# LED_volume_bar.net
KiCad netlist of a schematic drawn in EAGLE
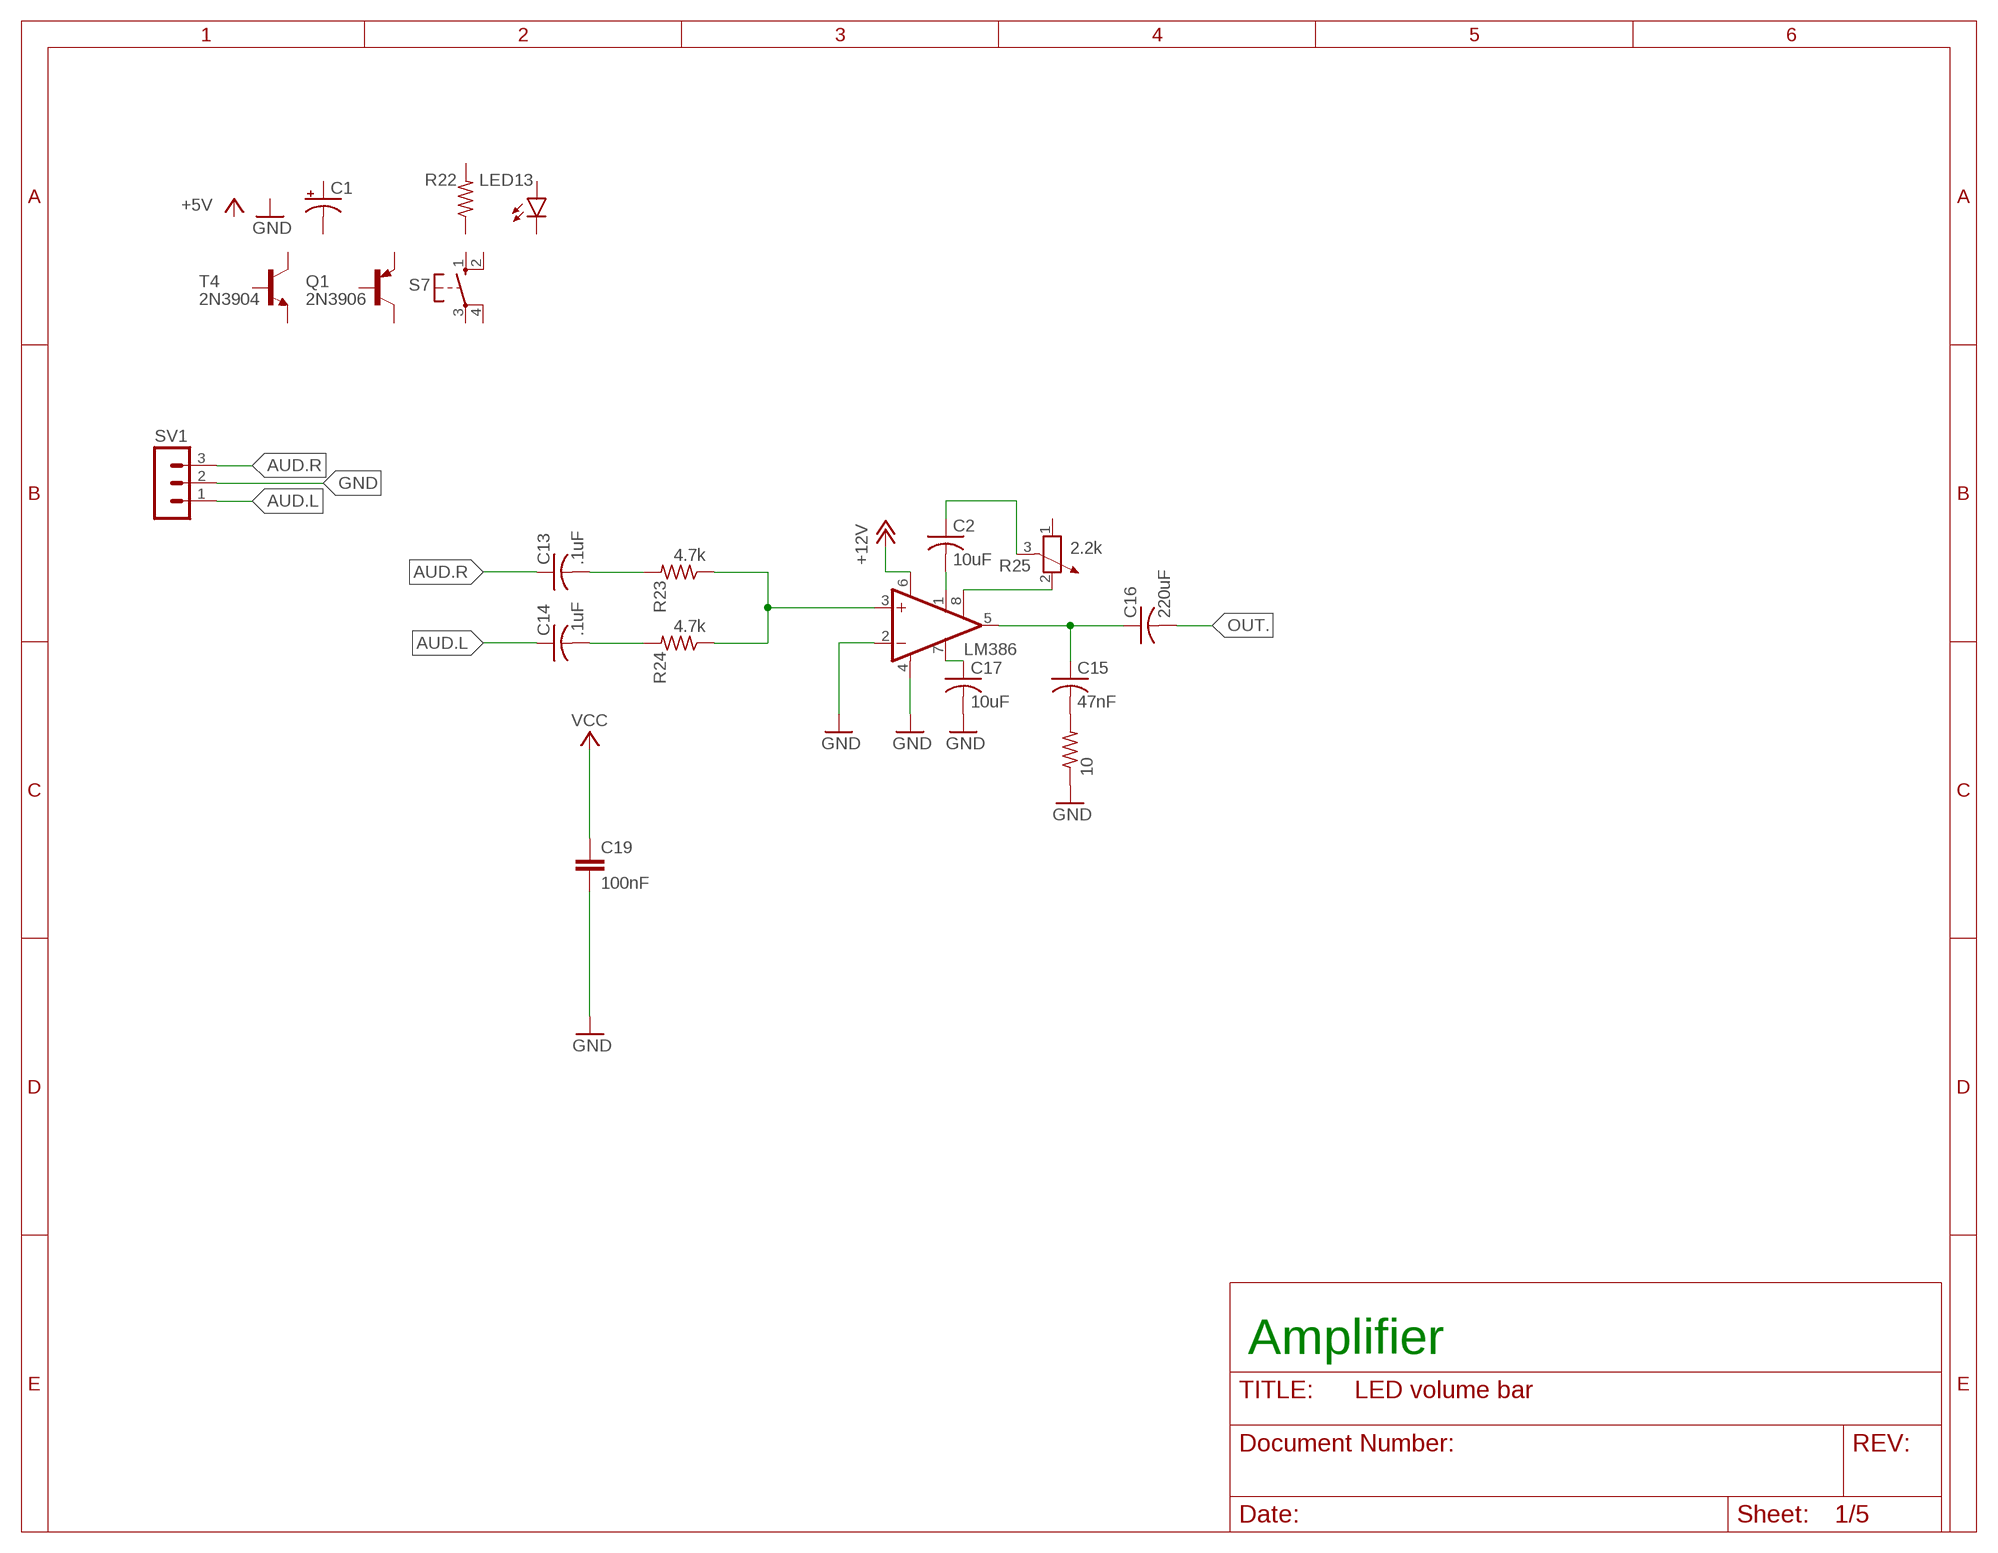
[diagram p0: schematic, sheet 1]
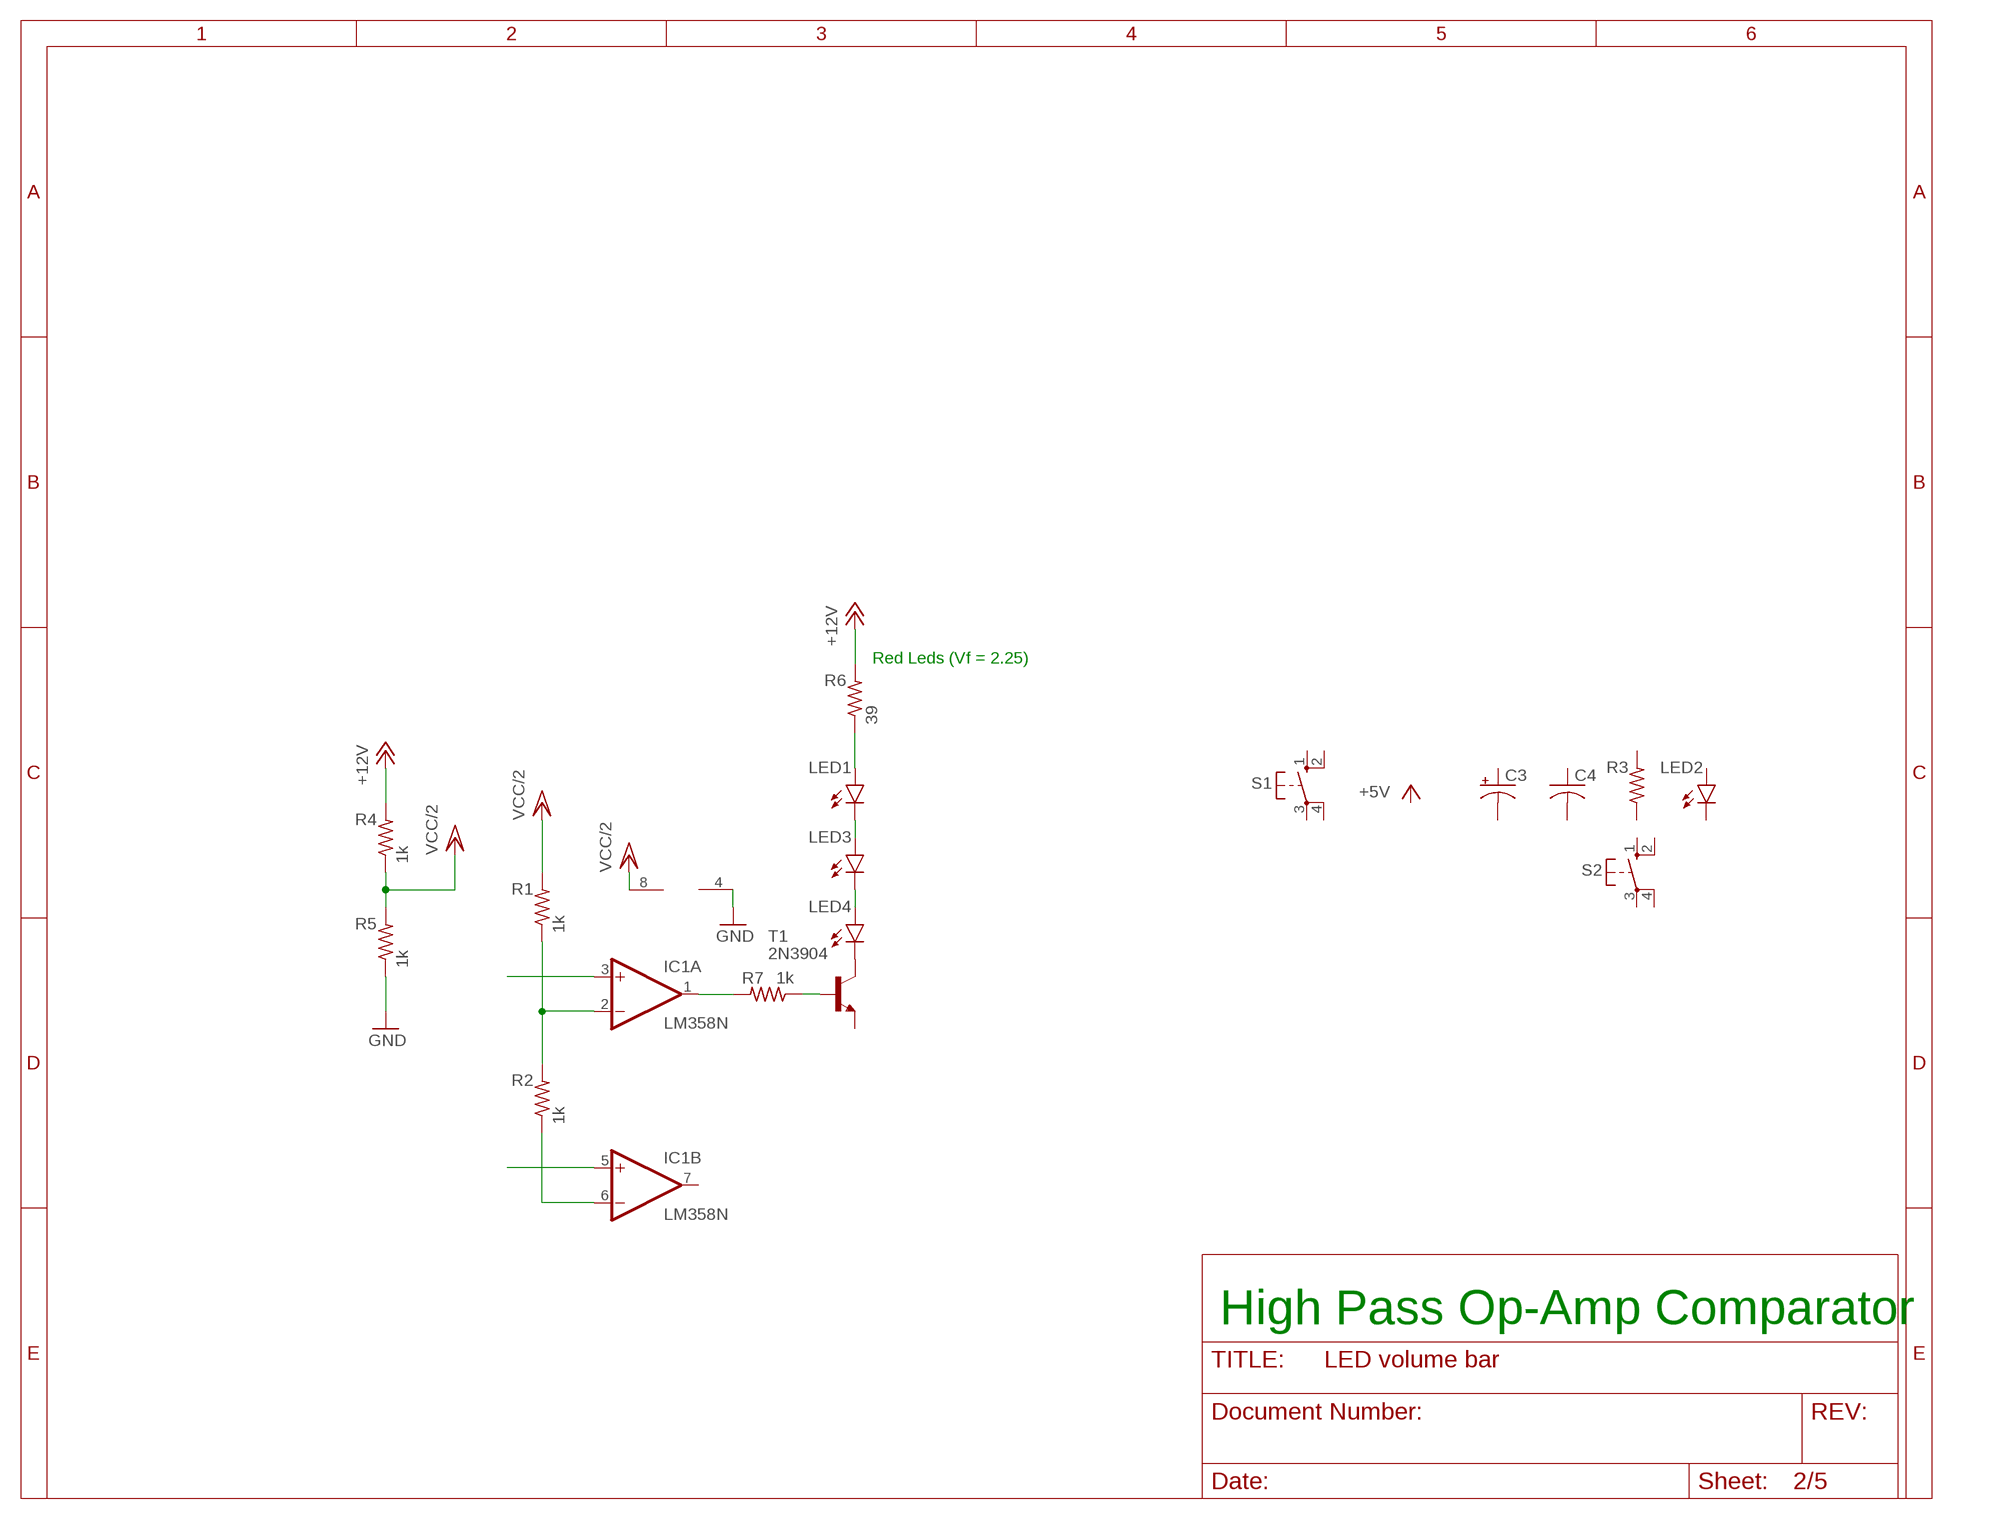
[diagram p1: schematic, sheet 2]
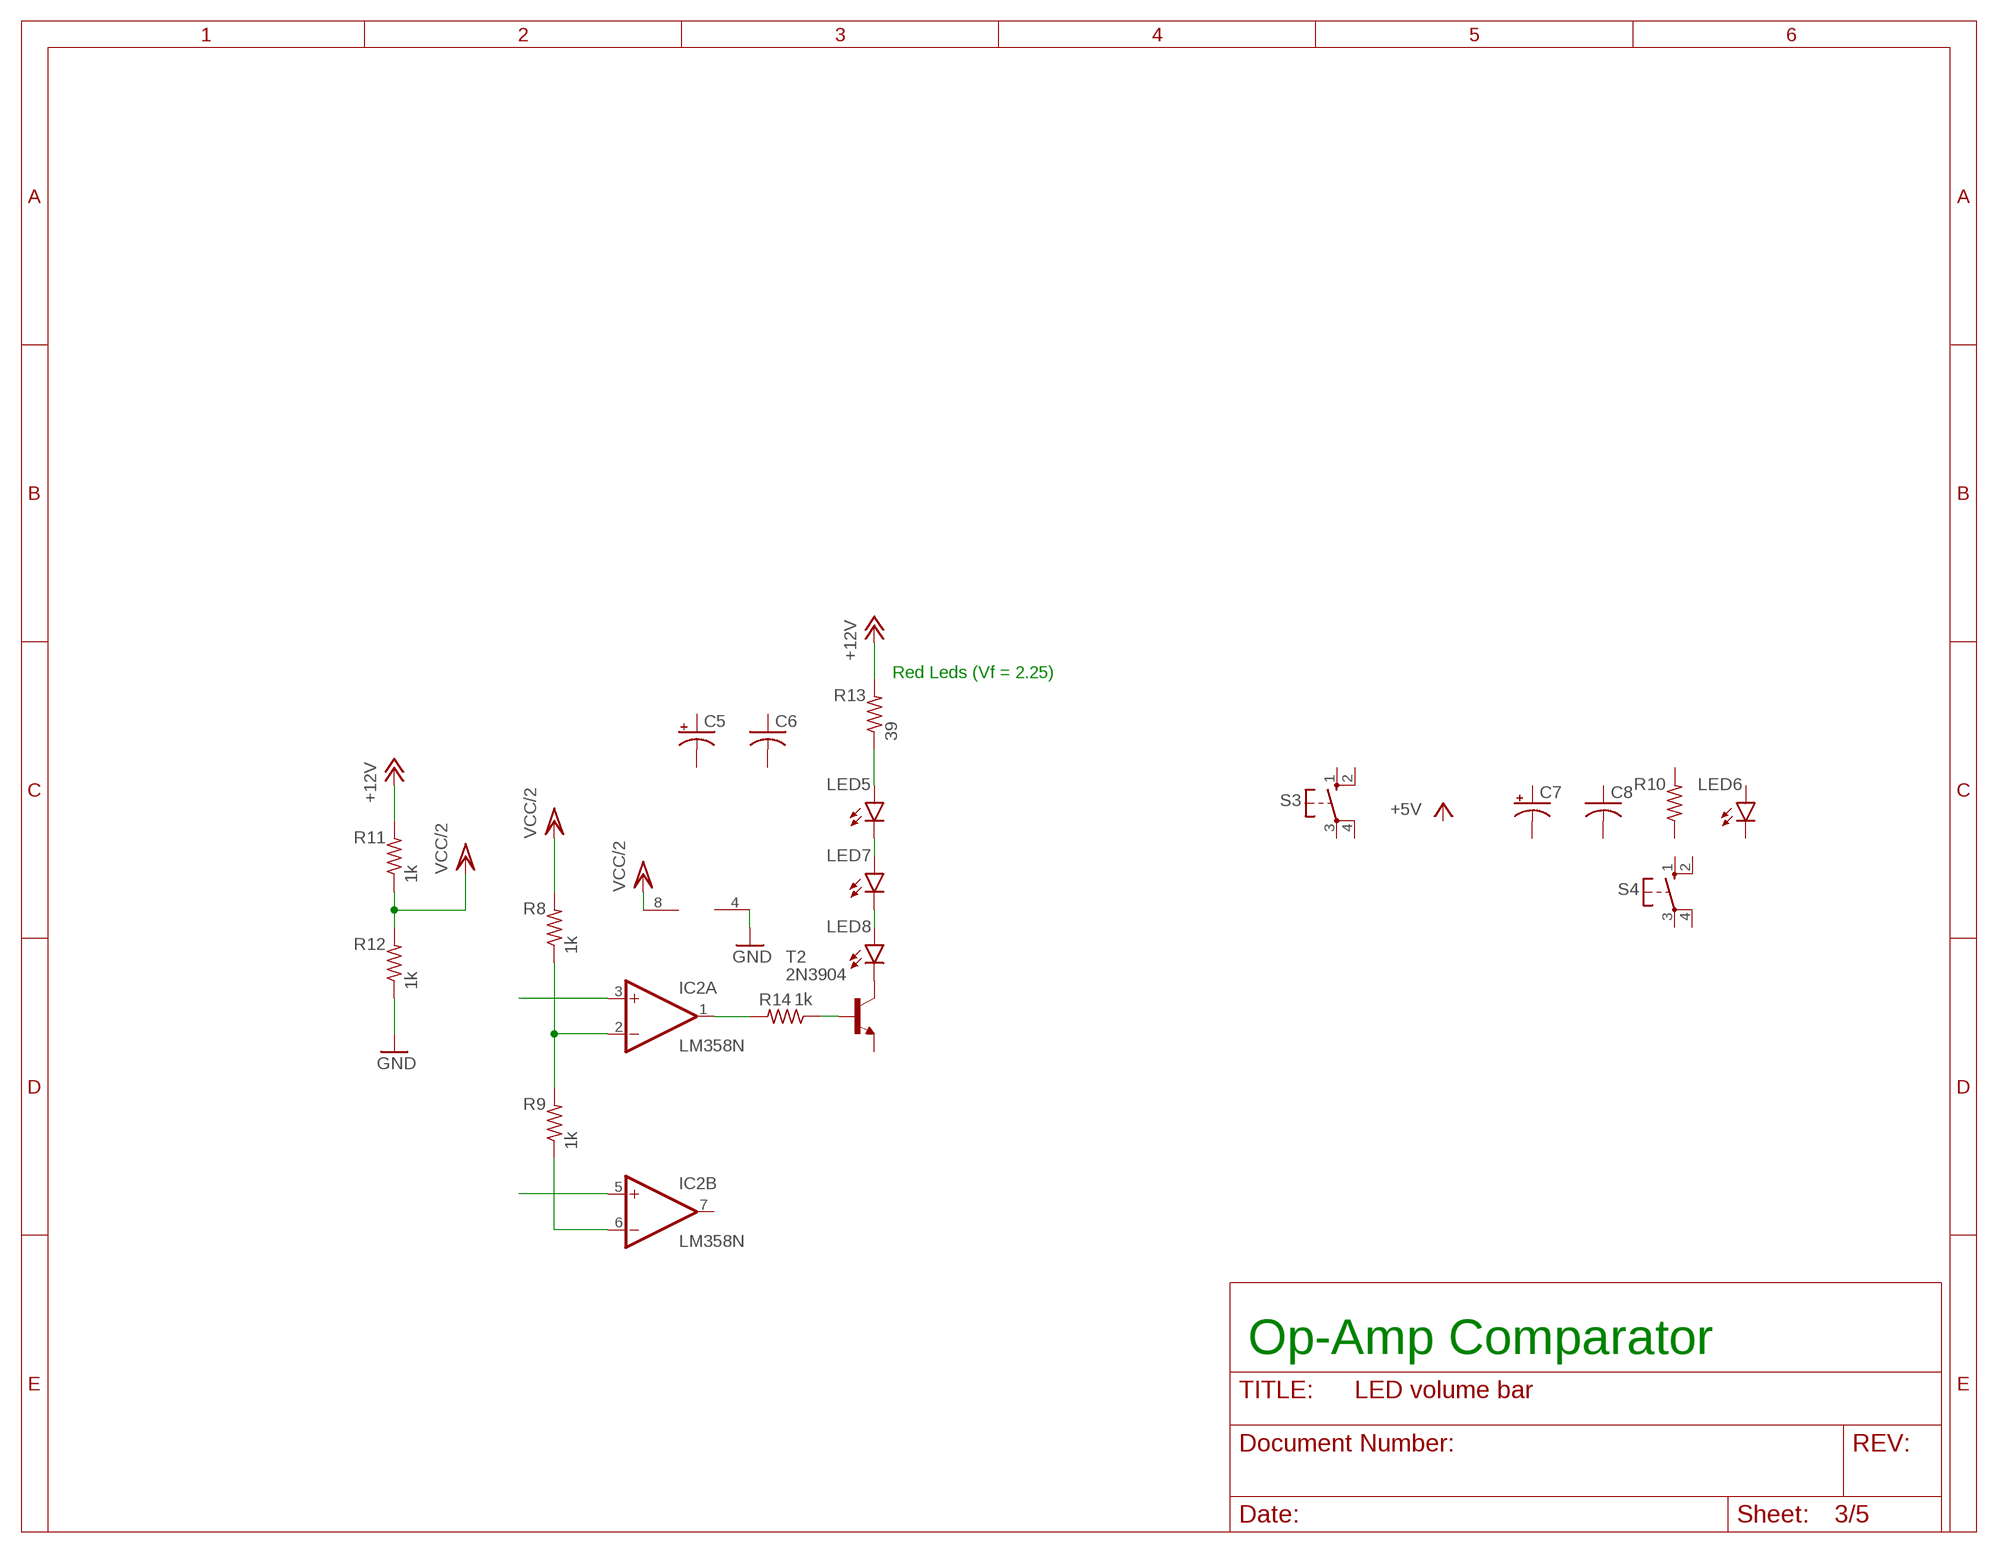
[diagram p2: schematic, sheet 3]
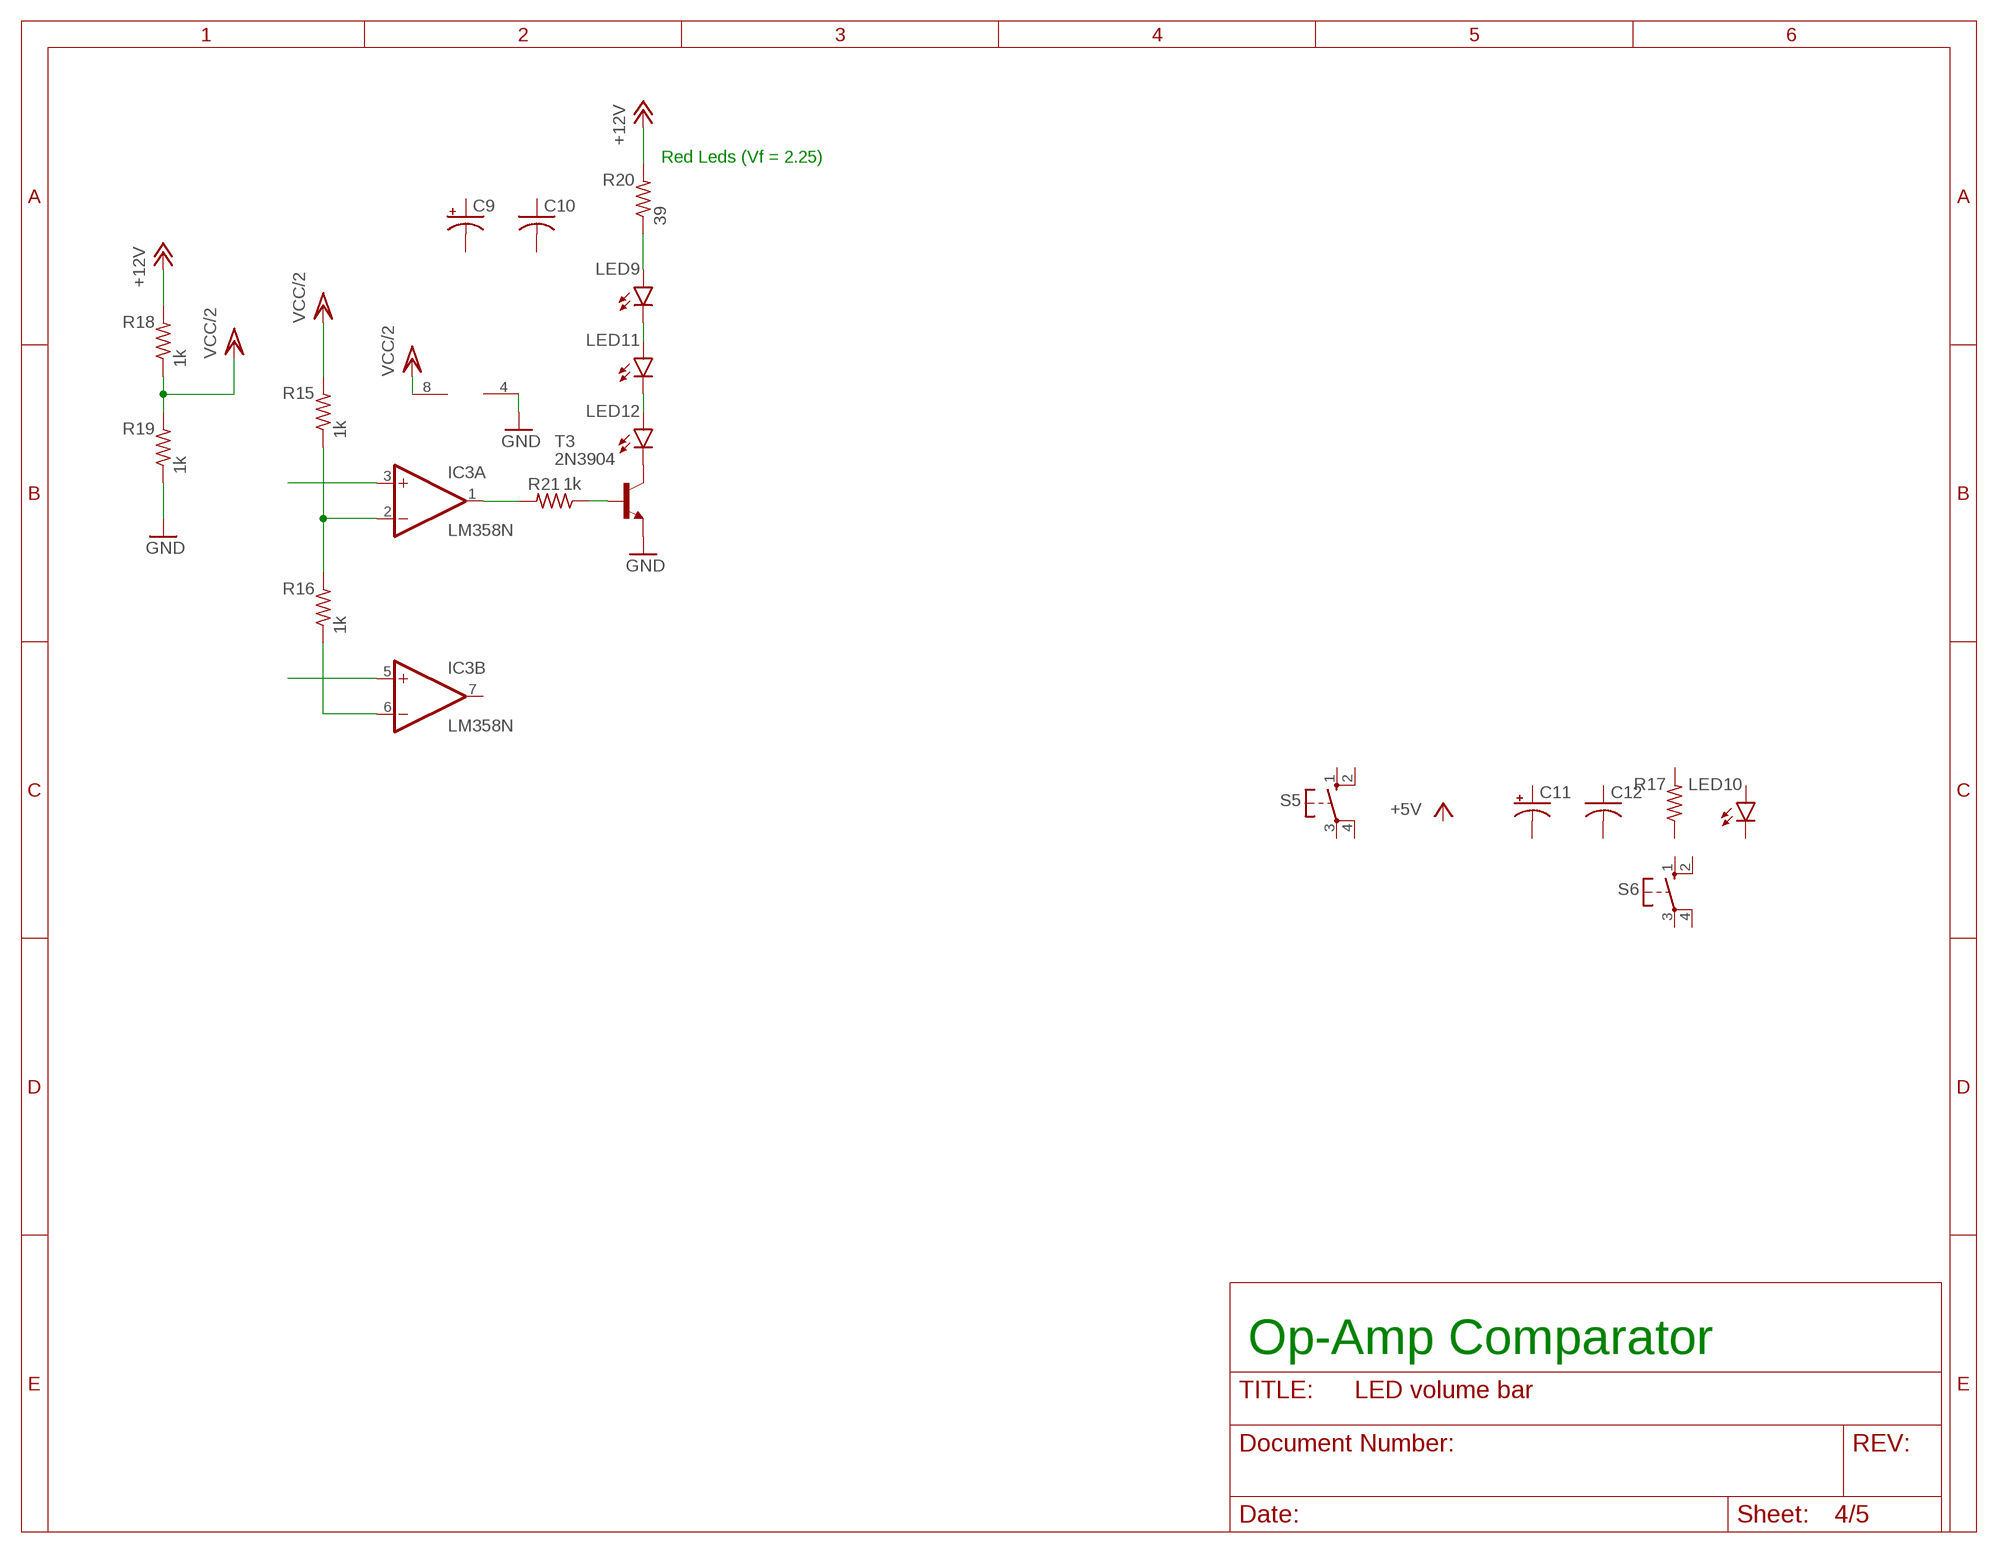
[diagram p3: schematic, sheet 4]

(export (version "E")
  (design (tool "Eeschema 10.0.6"))
  (components
    (comp (ref "C3")
      (value "CPOL-USE1.8-4")
      (footprint "eagle-import:E1,8-4")
      (libsource (lib "eagle-import") (part "CPOL-USE1.8-4"))
    )
    (comp (ref "C4")
      (value "C-US050-024X044")
      (footprint "eagle-import:C050-024X044")
      (libsource (lib "eagle-import") (part "C-US050-024X044"))
    )
    (comp (ref "IC1")
      (value "LM358N")
      (footprint "eagle-import:DIL08")
      (libsource (lib "eagle-import") (part "LM358N"))
    )
    (comp (ref "LED1")
      (value "LED5MM")
      (footprint "eagle-import:LED5MM")
      (libsource (lib "eagle-import") (part "LED5MM"))
    )
    (comp (ref "LED2")
      (value "LED5MM")
      (footprint "eagle-import:LED5MM")
      (libsource (lib "eagle-import") (part "LED5MM"))
    )
    (comp (ref "LED3")
      (value "LED5MM")
      (footprint "eagle-import:LED5MM")
      (libsource (lib "eagle-import") (part "LED5MM"))
    )
    (comp (ref "LED4")
      (value "LED5MM")
      (footprint "eagle-import:LED5MM")
      (libsource (lib "eagle-import") (part "LED5MM"))
    )
    (comp (ref "R1")
      (value "1k")
      (footprint "eagle-import:0207_12")
      (libsource (lib "eagle-import") (part "R-US_0207/12"))
    )
    (comp (ref "R2")
      (value "1k")
      (footprint "eagle-import:0207_12")
      (libsource (lib "eagle-import") (part "R-US_0207/12"))
    )
    (comp (ref "R3")
      (value "R-US_0207/12")
      (footprint "eagle-import:0207_12")
      (libsource (lib "eagle-import") (part "R-US_0207/12"))
    )
    (comp (ref "R4")
      (value "1k")
      (footprint "eagle-import:0207_12")
      (libsource (lib "eagle-import") (part "R-US_0207/12"))
    )
    (comp (ref "R5")
      (value "1k")
      (footprint "eagle-import:0207_12")
      (libsource (lib "eagle-import") (part "R-US_0207/12"))
    )
    (comp (ref "R6")
      (value "39")
      (footprint "eagle-import:0207_12")
      (libsource (lib "eagle-import") (part "R-US_0207/12"))
    )
    (comp (ref "R7")
      (value "1k")
      (footprint "eagle-import:0207_12")
      (libsource (lib "eagle-import") (part "R-US_0207/12"))
    )
    (comp (ref "S1")
      (value "10-XX")
      (footprint "eagle-import:B3F-10XX")
      (fields (field (name "MPN") "B3F-1000"))
      (libsource (lib "eagle-import") (part "10-XX"))
    )
    (comp (ref "S2")
      (value "10-XX")
      (footprint "eagle-import:B3F-10XX")
      (fields (field (name "MPN") "B3F-1000"))
      (libsource (lib "eagle-import") (part "10-XX"))
    )
    (comp (ref "T1")
      (value "2N3904")
      (footprint "eagle-import:TO92")
      (libsource (lib "eagle-import") (part "2N3904"))
    )
    (comp (ref "C9")
      (value "CPOL-USE1.8-4")
      (footprint "eagle-import:E1,8-4")
      (libsource (lib "eagle-import") (part "CPOL-USE1.8-4"))
    )
    (comp (ref "C10")
      (value "C-US050-024X044")
      (footprint "eagle-import:C050-024X044")
      (libsource (lib "eagle-import") (part "C-US050-024X044"))
    )
    (comp (ref "C11")
      (value "CPOL-USE1.8-4")
      (footprint "eagle-import:E1,8-4")
      (libsource (lib "eagle-import") (part "CPOL-USE1.8-4"))
    )
    (comp (ref "C12")
      (value "C-US050-024X044")
      (footprint "eagle-import:C050-024X044")
      (libsource (lib "eagle-import") (part "C-US050-024X044"))
    )
    (comp (ref "IC3")
      (value "LM358N")
      (footprint "eagle-import:DIL08")
      (libsource (lib "eagle-import") (part "LM358N"))
    )
    (comp (ref "LED9")
      (value "LED5MM")
      (footprint "eagle-import:LED5MM")
      (libsource (lib "eagle-import") (part "LED5MM"))
    )
    (comp (ref "LED10")
      (value "LED5MM")
      (footprint "eagle-import:LED5MM")
      (libsource (lib "eagle-import") (part "LED5MM"))
    )
    (comp (ref "LED11")
      (value "LED5MM")
      (footprint "eagle-import:LED5MM")
      (libsource (lib "eagle-import") (part "LED5MM"))
    )
    (comp (ref "LED12")
      (value "LED5MM")
      (footprint "eagle-import:LED5MM")
      (libsource (lib "eagle-import") (part "LED5MM"))
    )
    (comp (ref "R15")
      (value "1k")
      (footprint "eagle-import:0207_12")
      (libsource (lib "eagle-import") (part "R-US_0207/12"))
    )
    (comp (ref "R16")
      (value "1k")
      (footprint "eagle-import:0207_12")
      (libsource (lib "eagle-import") (part "R-US_0207/12"))
    )
    (comp (ref "R17")
      (value "R-US_0207/12")
      (footprint "eagle-import:0207_12")
      (libsource (lib "eagle-import") (part "R-US_0207/12"))
    )
    (comp (ref "R18")
      (value "1k")
      (footprint "eagle-import:0207_12")
      (libsource (lib "eagle-import") (part "R-US_0207/12"))
    )
    (comp (ref "R19")
      (value "1k")
      (footprint "eagle-import:0207_12")
      (libsource (lib "eagle-import") (part "R-US_0207/12"))
    )
    (comp (ref "R20")
      (value "39")
      (footprint "eagle-import:0207_12")
      (libsource (lib "eagle-import") (part "R-US_0207/12"))
    )
    (comp (ref "R21")
      (value "1k")
      (footprint "eagle-import:0207_12")
      (libsource (lib "eagle-import") (part "R-US_0207/12"))
    )
    (comp (ref "S5")
      (value "10-XX")
      (footprint "eagle-import:B3F-10XX")
      (fields (field (name "MPN") "B3F-1000"))
      (libsource (lib "eagle-import") (part "10-XX"))
    )
    (comp (ref "S6")
      (value "10-XX")
      (footprint "eagle-import:B3F-10XX")
      (fields (field (name "MPN") "B3F-1000"))
      (libsource (lib "eagle-import") (part "10-XX"))
    )
    (comp (ref "T3")
      (value "2N3904")
      (footprint "eagle-import:TO92")
      (libsource (lib "eagle-import") (part "2N3904"))
    )
    (comp (ref "C5")
      (value "CPOL-USE1.8-4")
      (footprint "eagle-import:E1,8-4")
      (libsource (lib "eagle-import") (part "CPOL-USE1.8-4"))
    )
    (comp (ref "C6")
      (value "C-US050-024X044")
      (footprint "eagle-import:C050-024X044")
      (libsource (lib "eagle-import") (part "C-US050-024X044"))
    )
    (comp (ref "C7")
      (value "CPOL-USE1.8-4")
      (footprint "eagle-import:E1,8-4")
      (libsource (lib "eagle-import") (part "CPOL-USE1.8-4"))
    )
    (comp (ref "C8")
      (value "C-US050-024X044")
      (footprint "eagle-import:C050-024X044")
      (libsource (lib "eagle-import") (part "C-US050-024X044"))
    )
    (comp (ref "IC2")
      (value "LM358N")
      (footprint "eagle-import:DIL08")
      (libsource (lib "eagle-import") (part "LM358N"))
    )
    (comp (ref "LED5")
      (value "LED5MM")
      (footprint "eagle-import:LED5MM")
      (libsource (lib "eagle-import") (part "LED5MM"))
    )
    (comp (ref "LED6")
      (value "LED5MM")
      (footprint "eagle-import:LED5MM")
      (libsource (lib "eagle-import") (part "LED5MM"))
    )
    (comp (ref "LED7")
      (value "LED5MM")
      (footprint "eagle-import:LED5MM")
      (libsource (lib "eagle-import") (part "LED5MM"))
    )
    (comp (ref "LED8")
      (value "LED5MM")
      (footprint "eagle-import:LED5MM")
      (libsource (lib "eagle-import") (part "LED5MM"))
    )
    (comp (ref "R8")
      (value "1k")
      (footprint "eagle-import:0207_12")
      (libsource (lib "eagle-import") (part "R-US_0207/12"))
    )
    (comp (ref "R9")
      (value "1k")
      (footprint "eagle-import:0207_12")
      (libsource (lib "eagle-import") (part "R-US_0207/12"))
    )
    (comp (ref "R10")
      (value "R-US_0207/12")
      (footprint "eagle-import:0207_12")
      (libsource (lib "eagle-import") (part "R-US_0207/12"))
    )
    (comp (ref "R11")
      (value "1k")
      (footprint "eagle-import:0207_12")
      (libsource (lib "eagle-import") (part "R-US_0207/12"))
    )
    (comp (ref "R12")
      (value "1k")
      (footprint "eagle-import:0207_12")
      (libsource (lib "eagle-import") (part "R-US_0207/12"))
    )
    (comp (ref "R13")
      (value "39")
      (footprint "eagle-import:0207_12")
      (libsource (lib "eagle-import") (part "R-US_0207/12"))
    )
    (comp (ref "R14")
      (value "1k")
      (footprint "eagle-import:0207_12")
      (libsource (lib "eagle-import") (part "R-US_0207/12"))
    )
    (comp (ref "S3")
      (value "10-XX")
      (footprint "eagle-import:B3F-10XX")
      (fields (field (name "MPN") "B3F-1000"))
      (libsource (lib "eagle-import") (part "10-XX"))
    )
    (comp (ref "S4")
      (value "10-XX")
      (footprint "eagle-import:B3F-10XX")
      (fields (field (name "MPN") "B3F-1000"))
      (libsource (lib "eagle-import") (part "10-XX"))
    )
    (comp (ref "T2")
      (value "2N3904")
      (footprint "eagle-import:TO92")
      (libsource (lib "eagle-import") (part "2N3904"))
    )
    (comp (ref "C1")
      (value "CPOL-USE1.8-4")
      (footprint "eagle-import:E1,8-4")
      (libsource (lib "eagle-import") (part "CPOL-USE1.8-4"))
    )
    (comp (ref "C2")
      (value "10uF")
      (footprint "eagle-import:C050-024X044")
      (libsource (lib "eagle-import") (part "C-US050-024X044"))
    )
    (comp (ref "C13")
      (value ".1uF")
      (footprint "eagle-import:C050-024X044")
      (libsource (lib "eagle-import") (part "C-US050-024X044"))
    )
    (comp (ref "C14")
      (value ".1uF")
      (footprint "eagle-import:C050-024X044")
      (libsource (lib "eagle-import") (part "C-US050-024X044"))
    )
    (comp (ref "C15")
      (value "47nF")
      (footprint "eagle-import:C050-024X044")
      (libsource (lib "eagle-import") (part "C-US050-024X044"))
    )
    (comp (ref "C16")
      (value "220uF")
      (footprint "eagle-import:C050-024X044")
      (libsource (lib "eagle-import") (part "C-US050-024X044"))
    )
    (comp (ref "C17")
      (value "10uF")
      (footprint "eagle-import:C050-024X044")
      (libsource (lib "eagle-import") (part "C-US050-024X044"))
    )
    (comp (ref "C19")
      (value "100nF")
      (footprint "eagle-import:C025-025X050")
      (libsource (lib "eagle-import") (part "C-EU025-025X050"))
    )
    (comp (ref "LED13")
      (value "LED5MM")
      (footprint "eagle-import:LED5MM")
      (libsource (lib "eagle-import") (part "LED5MM"))
    )
    (comp (ref "LM386")
      (value "LM386N-1")
      (footprint "eagle-import:DIL08")
      (libsource (lib "eagle-import") (part "LM386?-N1"))
    )
    (comp (ref "Q1")
      (value "2N3906")
      (footprint "eagle-import:TO92")
      (libsource (lib "eagle-import") (part "2N3906"))
    )
    (comp (ref "R22")
      (value "R-US_0207/12")
      (footprint "eagle-import:0207_12")
      (libsource (lib "eagle-import") (part "R-US_0207/12"))
    )
    (comp (ref "R23")
      (value "4.7k")
      (footprint "eagle-import:0207_12")
      (libsource (lib "eagle-import") (part "R-US_0207/12"))
    )
    (comp (ref "R24")
      (value "4.7k")
      (footprint "eagle-import:0207_12")
      (libsource (lib "eagle-import") (part "R-US_0207/12"))
    )
    (comp (ref "R25")
      (value "2.2k")
      (footprint "eagle-import:PT-10S")
      (libsource (lib "eagle-import") (part "POTENTIOMETER_PT-10S"))
    )
    (comp (ref "R26")
      (value "10")
      (footprint "eagle-import:0207_12")
      (libsource (lib "eagle-import") (part "R-US_0207/12"))
    )
    (comp (ref "S7")
      (value "10-XX")
      (footprint "eagle-import:B3F-10XX")
      (fields (field (name "MPN") "B3F-1000"))
      (libsource (lib "eagle-import") (part "10-XX"))
    )
    (comp (ref "SV1")
      (value "MA03-1")
      (footprint "eagle-import:MA03-1")
      (libsource (lib "eagle-import") (part "MA03-1"))
    )
    (comp (ref "T4")
      (value "2N3904")
      (footprint "eagle-import:TO92")
      (libsource (lib "eagle-import") (part "2N3904"))
    )
  )
  (nets
    (net (code "2") (name "+12V") (class "Default")
      (node (ref "LM386") (pin "6") (pinfunction "VS_6") (pintype "power_in"))
      (node (ref "R11") (pin "2") (pinfunction "2_2") (pintype "passive"))
      (node (ref "R13") (pin "2") (pinfunction "2_2") (pintype "passive"))
      (node (ref "R18") (pin "2") (pinfunction "2_2") (pintype "passive"))
      (node (ref "R20") (pin "2") (pinfunction "2_2") (pintype "passive"))
      (node (ref "R4") (pin "2") (pinfunction "2_2") (pintype "passive"))
      (node (ref "R6") (pin "2") (pinfunction "2_2") (pintype "passive"))
    )
    (net (code "3") (name "AUD.L") (class "Default")
      (node (ref "C14") (pin "1") (pinfunction "1_1") (pintype "passive"))
      (node (ref "SV1") (pin "1") (pinfunction "1_1") (pintype "passive"))
    )
    (net (code "4") (name "AUD.R") (class "Default")
      (node (ref "C13") (pin "1") (pinfunction "1_1") (pintype "passive"))
      (node (ref "SV1") (pin "3") (pinfunction "3_3") (pintype "passive"))
    )
    (net (code "5") (name "GND") (class "Default")
      (node (ref "C17") (pin "2") (pinfunction "2_2") (pintype "passive"))
      (node (ref "C19") (pin "2") (pinfunction "2_2") (pintype "passive"))
      (node (ref "IC1") (pin "4") (pinfunction "V-_4") (pintype "power_in"))
      (node (ref "IC2") (pin "4") (pinfunction "V-_4") (pintype "power_in"))
      (node (ref "IC3") (pin "4") (pinfunction "V-_4") (pintype "power_in"))
      (node (ref "LM386") (pin "2") (pinfunction "-IN_2") (pintype "input"))
      (node (ref "LM386") (pin "4") (pinfunction "GND_4") (pintype "power_in"))
      (node (ref "R12") (pin "1") (pinfunction "1_1") (pintype "passive"))
      (node (ref "R19") (pin "1") (pinfunction "1_1") (pintype "passive"))
      (node (ref "R26") (pin "1") (pinfunction "1_1") (pintype "passive"))
      (node (ref "R5") (pin "1") (pinfunction "1_1") (pintype "passive"))
      (node (ref "SV1") (pin "2") (pinfunction "2_2") (pintype "passive"))
      (node (ref "T3") (pin "3") (pinfunction "E_3") (pintype "passive"))
    )
    (net (code "6") (name "Net-(C2-Pad1)") (class "Default")
      (node (ref "C2") (pin "1") (pinfunction "1_1") (pintype "passive"))
      (node (ref "R25") (pin "3") (pinfunction "3_3") (pintype "passive"))
    )
    (net (code "7") (name "Net-(C2-Pad2)") (class "Default")
      (node (ref "C2") (pin "2") (pinfunction "2_2") (pintype "passive"))
      (node (ref "LM386") (pin "1") (pinfunction "GAIN_1") (pintype "passive"))
    )
    (net (code "8") (name "Net-(C13-Pad2)") (class "Default")
      (node (ref "C13") (pin "2") (pinfunction "2_2") (pintype "passive"))
      (node (ref "R23") (pin "2") (pinfunction "2_2") (pintype "passive"))
    )
    (net (code "9") (name "Net-(C14-Pad2)") (class "Default")
      (node (ref "C14") (pin "2") (pinfunction "2_2") (pintype "passive"))
      (node (ref "R24") (pin "2") (pinfunction "2_2") (pintype "passive"))
    )
    (net (code "10") (name "Net-(C15-Pad2)") (class "Default")
      (node (ref "C15") (pin "2") (pinfunction "2_2") (pintype "passive"))
      (node (ref "R26") (pin "2") (pinfunction "2_2") (pintype "passive"))
    )
    (net (code "11") (name "Net-(IC1A--IN)") (class "Default")
      (node (ref "IC1") (pin "2") (pinfunction "-IN_2") (pintype "input"))
      (node (ref "R1") (pin "1") (pinfunction "1_1") (pintype "passive"))
      (node (ref "R2") (pin "2") (pinfunction "2_2") (pintype "passive"))
    )
    (net (code "12") (name "Net-(IC1A-OUT)") (class "Default")
      (node (ref "IC1") (pin "1") (pinfunction "OUT_1") (pintype "output"))
      (node (ref "R7") (pin "2") (pinfunction "2_2") (pintype "passive"))
    )
    (net (code "13") (name "Net-(IC1B--IN)") (class "Default")
      (node (ref "IC1") (pin "6") (pinfunction "-IN_6") (pintype "input"))
      (node (ref "R2") (pin "1") (pinfunction "1_1") (pintype "passive"))
    )
    (net (code "14") (name "Net-(IC2A--IN)") (class "Default")
      (node (ref "IC2") (pin "2") (pinfunction "-IN_2") (pintype "input"))
      (node (ref "R8") (pin "1") (pinfunction "1_1") (pintype "passive"))
      (node (ref "R9") (pin "2") (pinfunction "2_2") (pintype "passive"))
    )
    (net (code "15") (name "Net-(IC2A-OUT)") (class "Default")
      (node (ref "IC2") (pin "1") (pinfunction "OUT_1") (pintype "output"))
      (node (ref "R14") (pin "2") (pinfunction "2_2") (pintype "passive"))
    )
    (net (code "16") (name "Net-(IC2B--IN)") (class "Default")
      (node (ref "IC2") (pin "6") (pinfunction "-IN_6") (pintype "input"))
      (node (ref "R9") (pin "1") (pinfunction "1_1") (pintype "passive"))
    )
    (net (code "17") (name "Net-(IC3A--IN)") (class "Default")
      (node (ref "IC3") (pin "2") (pinfunction "-IN_2") (pintype "input"))
      (node (ref "R15") (pin "1") (pinfunction "1_1") (pintype "passive"))
      (node (ref "R16") (pin "2") (pinfunction "2_2") (pintype "passive"))
    )
    (net (code "18") (name "Net-(IC3A-OUT)") (class "Default")
      (node (ref "IC3") (pin "1") (pinfunction "OUT_1") (pintype "output"))
      (node (ref "R21") (pin "2") (pinfunction "2_2") (pintype "passive"))
    )
    (net (code "19") (name "Net-(IC3B--IN)") (class "Default")
      (node (ref "IC3") (pin "6") (pinfunction "-IN_6") (pintype "input"))
      (node (ref "R16") (pin "1") (pinfunction "1_1") (pintype "passive"))
    )
    (net (code "20") (name "Net-(LED1-C)") (class "Default")
      (node (ref "LED1") (pin "K") (pinfunction "C_K") (pintype "passive"))
      (node (ref "LED3") (pin "A") (pinfunction "A_A") (pintype "passive"))
    )
    (net (code "21") (name "Net-(LED1-PadA)") (class "Default")
      (node (ref "LED1") (pin "A") (pinfunction "A_A") (pintype "passive"))
      (node (ref "R6") (pin "1") (pinfunction "1_1") (pintype "passive"))
    )
    (net (code "22") (name "Net-(LED3-C)") (class "Default")
      (node (ref "LED3") (pin "K") (pinfunction "C_K") (pintype "passive"))
      (node (ref "LED4") (pin "A") (pinfunction "A_A") (pintype "passive"))
    )
    (net (code "23") (name "Net-(LED4-C)") (class "Default")
      (node (ref "LED4") (pin "K") (pinfunction "C_K") (pintype "passive"))
      (node (ref "T1") (pin "1") (pinfunction "C_1") (pintype "passive"))
    )
    (net (code "24") (name "Net-(LED5-C)") (class "Default")
      (node (ref "LED5") (pin "K") (pinfunction "C_K") (pintype "passive"))
      (node (ref "LED7") (pin "A") (pinfunction "A_A") (pintype "passive"))
    )
    (net (code "25") (name "Net-(LED5-PadA)") (class "Default")
      (node (ref "LED5") (pin "A") (pinfunction "A_A") (pintype "passive"))
      (node (ref "R13") (pin "1") (pinfunction "1_1") (pintype "passive"))
    )
    (net (code "26") (name "Net-(LED7-C)") (class "Default")
      (node (ref "LED7") (pin "K") (pinfunction "C_K") (pintype "passive"))
      (node (ref "LED8") (pin "A") (pinfunction "A_A") (pintype "passive"))
    )
    (net (code "27") (name "Net-(LED8-C)") (class "Default")
      (node (ref "LED8") (pin "K") (pinfunction "C_K") (pintype "passive"))
      (node (ref "T2") (pin "1") (pinfunction "C_1") (pintype "passive"))
    )
    (net (code "28") (name "Net-(LED9-C)") (class "Default")
      (node (ref "LED11") (pin "A") (pinfunction "A_A") (pintype "passive"))
      (node (ref "LED9") (pin "K") (pinfunction "C_K") (pintype "passive"))
    )
    (net (code "29") (name "Net-(LED9-PadA)") (class "Default")
      (node (ref "LED9") (pin "A") (pinfunction "A_A") (pintype "passive"))
      (node (ref "R20") (pin "1") (pinfunction "1_1") (pintype "passive"))
    )
    (net (code "30") (name "Net-(LED11-C)") (class "Default")
      (node (ref "LED11") (pin "K") (pinfunction "C_K") (pintype "passive"))
      (node (ref "LED12") (pin "A") (pinfunction "A_A") (pintype "passive"))
    )
    (net (code "31") (name "Net-(LED12-C)") (class "Default")
      (node (ref "LED12") (pin "K") (pinfunction "C_K") (pintype "passive"))
      (node (ref "T3") (pin "1") (pinfunction "C_1") (pintype "passive"))
    )
    (net (code "32") (name "Net-(LM386-+IN)") (class "Default")
      (node (ref "LM386") (pin "3") (pinfunction "+IN_3") (pintype "input"))
      (node (ref "R23") (pin "1") (pinfunction "1_1") (pintype "passive"))
      (node (ref "R24") (pin "1") (pinfunction "1_1") (pintype "passive"))
    )
    (net (code "33") (name "Net-(LM386-BYPASS)") (class "Default")
      (node (ref "C17") (pin "1") (pinfunction "1_1") (pintype "passive"))
      (node (ref "LM386") (pin "7") (pinfunction "BYPASS_7") (pintype "passive"))
    )
    (net (code "34") (name "Net-(LM386-GAIN-Pad8)") (class "Default")
      (node (ref "LM386") (pin "8") (pinfunction "GAIN_8") (pintype "passive"))
      (node (ref "R25") (pin "2") (pinfunction "2_2") (pintype "passive"))
    )
    (net (code "35") (name "Net-(LM386-OUT)") (class "Default")
      (node (ref "C15") (pin "1") (pinfunction "1_1") (pintype "passive"))
      (node (ref "C16") (pin "1") (pinfunction "1_1") (pintype "passive"))
      (node (ref "LM386") (pin "5") (pinfunction "OUT_5") (pintype "output"))
    )
    (net (code "36") (name "Net-(T1-B)") (class "Default")
      (node (ref "R7") (pin "1") (pinfunction "1_1") (pintype "passive"))
      (node (ref "T1") (pin "2") (pinfunction "B_2") (pintype "passive"))
    )
    (net (code "37") (name "Net-(T2-B)") (class "Default")
      (node (ref "R14") (pin "1") (pinfunction "1_1") (pintype "passive"))
      (node (ref "T2") (pin "2") (pinfunction "B_2") (pintype "passive"))
    )
    (net (code "38") (name "Net-(T3-B)") (class "Default")
      (node (ref "R21") (pin "1") (pinfunction "1_1") (pintype "passive"))
      (node (ref "T3") (pin "2") (pinfunction "B_2") (pintype "passive"))
    )
    (net (code "39") (name "OUT.") (class "Default")
      (node (ref "C16") (pin "2") (pinfunction "2_2") (pintype "passive"))
    )
    (net (code "40") (name "VCC") (class "Default")
      (node (ref "C19") (pin "1") (pinfunction "1_1") (pintype "passive"))
    )
    (net (code "41") (name "VCC{slash}2") (class "Default")
      (node (ref "IC1") (pin "8") (pinfunction "V+_8") (pintype "power_in"))
      (node (ref "IC2") (pin "8") (pinfunction "V+_8") (pintype "power_in"))
      (node (ref "IC3") (pin "8") (pinfunction "V+_8") (pintype "power_in"))
      (node (ref "R1") (pin "2") (pinfunction "2_2") (pintype "passive"))
      (node (ref "R11") (pin "1") (pinfunction "1_1") (pintype "passive"))
      (node (ref "R12") (pin "2") (pinfunction "2_2") (pintype "passive"))
      (node (ref "R15") (pin "2") (pinfunction "2_2") (pintype "passive"))
      (node (ref "R18") (pin "1") (pinfunction "1_1") (pintype "passive"))
      (node (ref "R19") (pin "2") (pinfunction "2_2") (pintype "passive"))
      (node (ref "R4") (pin "1") (pinfunction "1_1") (pintype "passive"))
      (node (ref "R5") (pin "2") (pinfunction "2_2") (pintype "passive"))
      (node (ref "R8") (pin "2") (pinfunction "2_2") (pintype "passive"))
    )
    (net (code "42") (name "unconnected-(C1-Pad+)") (class "Default")
      (node (ref "C1") (pin "+") (pinfunction "+_+") (pintype "passive"))
    )
    (net (code "43") (name "unconnected-(C1-Pad-)") (class "Default")
      (node (ref "C1") (pin "-") (pinfunction "-_-") (pintype "passive"))
    )
    (net (code "44") (name "unconnected-(C3-Pad+)") (class "Default")
      (node (ref "C3") (pin "+") (pinfunction "+_+") (pintype "passive"))
    )
    (net (code "45") (name "unconnected-(C3-Pad-)") (class "Default")
      (node (ref "C3") (pin "-") (pinfunction "-_-") (pintype "passive"))
    )
    (net (code "46") (name "unconnected-(C4-Pad1)") (class "Default")
      (node (ref "C4") (pin "1") (pinfunction "1_1") (pintype "passive"))
    )
    (net (code "47") (name "unconnected-(C4-Pad2)") (class "Default")
      (node (ref "C4") (pin "2") (pinfunction "2_2") (pintype "passive"))
    )
    (net (code "48") (name "unconnected-(C5-Pad+)") (class "Default")
      (node (ref "C5") (pin "+") (pinfunction "+_+") (pintype "passive"))
    )
    (net (code "49") (name "unconnected-(C5-Pad-)") (class "Default")
      (node (ref "C5") (pin "-") (pinfunction "-_-") (pintype "passive"))
    )
    (net (code "50") (name "unconnected-(C6-Pad1)") (class "Default")
      (node (ref "C6") (pin "1") (pinfunction "1_1") (pintype "passive"))
    )
    (net (code "51") (name "unconnected-(C6-Pad2)") (class "Default")
      (node (ref "C6") (pin "2") (pinfunction "2_2") (pintype "passive"))
    )
    (net (code "52") (name "unconnected-(C7-Pad+)") (class "Default")
      (node (ref "C7") (pin "+") (pinfunction "+_+") (pintype "passive"))
    )
    (net (code "53") (name "unconnected-(C7-Pad-)") (class "Default")
      (node (ref "C7") (pin "-") (pinfunction "-_-") (pintype "passive"))
    )
    (net (code "54") (name "unconnected-(C8-Pad1)") (class "Default")
      (node (ref "C8") (pin "1") (pinfunction "1_1") (pintype "passive"))
    )
    (net (code "55") (name "unconnected-(C8-Pad2)") (class "Default")
      (node (ref "C8") (pin "2") (pinfunction "2_2") (pintype "passive"))
    )
    (net (code "56") (name "unconnected-(C9-Pad+)") (class "Default")
      (node (ref "C9") (pin "+") (pinfunction "+_+") (pintype "passive"))
    )
    (net (code "57") (name "unconnected-(C9-Pad-)") (class "Default")
      (node (ref "C9") (pin "-") (pinfunction "-_-") (pintype "passive"))
    )
    (net (code "58") (name "unconnected-(C10-Pad1)") (class "Default")
      (node (ref "C10") (pin "1") (pinfunction "1_1") (pintype "passive"))
    )
    (net (code "59") (name "unconnected-(C10-Pad2)") (class "Default")
      (node (ref "C10") (pin "2") (pinfunction "2_2") (pintype "passive"))
    )
    (net (code "60") (name "unconnected-(C11-Pad+)") (class "Default")
      (node (ref "C11") (pin "+") (pinfunction "+_+") (pintype "passive"))
    )
    (net (code "61") (name "unconnected-(C11-Pad-)") (class "Default")
      (node (ref "C11") (pin "-") (pinfunction "-_-") (pintype "passive"))
    )
    (net (code "62") (name "unconnected-(C12-Pad1)") (class "Default")
      (node (ref "C12") (pin "1") (pinfunction "1_1") (pintype "passive"))
    )
    (net (code "63") (name "unconnected-(C12-Pad2)") (class "Default")
      (node (ref "C12") (pin "2") (pinfunction "2_2") (pintype "passive"))
    )
    (net (code "64") (name "unconnected-(IC1A-+IN-Pad3)") (class "Default")
      (node (ref "IC1") (pin "3") (pinfunction "+IN_3") (pintype "input"))
    )
    (net (code "65") (name "unconnected-(IC1B-+IN-Pad5)") (class "Default")
      (node (ref "IC1") (pin "5") (pinfunction "+IN_5") (pintype "input"))
    )
    (net (code "66") (name "unconnected-(IC1B-OUT-Pad7)") (class "Default")
      (node (ref "IC1") (pin "7") (pinfunction "OUT_7") (pintype "output"))
    )
    (net (code "67") (name "unconnected-(IC2A-+IN-Pad3)") (class "Default")
      (node (ref "IC2") (pin "3") (pinfunction "+IN_3") (pintype "input"))
    )
    (net (code "68") (name "unconnected-(IC2B-+IN-Pad5)") (class "Default")
      (node (ref "IC2") (pin "5") (pinfunction "+IN_5") (pintype "input"))
    )
    (net (code "69") (name "unconnected-(IC2B-OUT-Pad7)") (class "Default")
      (node (ref "IC2") (pin "7") (pinfunction "OUT_7") (pintype "output"))
    )
    (net (code "70") (name "unconnected-(IC3A-+IN-Pad3)") (class "Default")
      (node (ref "IC3") (pin "3") (pinfunction "+IN_3") (pintype "input"))
    )
    (net (code "71") (name "unconnected-(IC3B-+IN-Pad5)") (class "Default")
      (node (ref "IC3") (pin "5") (pinfunction "+IN_5") (pintype "input"))
    )
    (net (code "72") (name "unconnected-(IC3B-OUT-Pad7)") (class "Default")
      (node (ref "IC3") (pin "7") (pinfunction "OUT_7") (pintype "output"))
    )
    (net (code "73") (name "unconnected-(LED2-C-PadK)") (class "Default")
      (node (ref "LED2") (pin "K") (pinfunction "C_K") (pintype "passive"))
    )
    (net (code "74") (name "unconnected-(LED2-PadA)") (class "Default")
      (node (ref "LED2") (pin "A") (pinfunction "A_A") (pintype "passive"))
    )
    (net (code "75") (name "unconnected-(LED6-C-PadK)") (class "Default")
      (node (ref "LED6") (pin "K") (pinfunction "C_K") (pintype "passive"))
    )
    (net (code "76") (name "unconnected-(LED6-PadA)") (class "Default")
      (node (ref "LED6") (pin "A") (pinfunction "A_A") (pintype "passive"))
    )
    (net (code "77") (name "unconnected-(LED10-C-PadK)") (class "Default")
      (node (ref "LED10") (pin "K") (pinfunction "C_K") (pintype "passive"))
    )
    (net (code "78") (name "unconnected-(LED10-PadA)") (class "Default")
      (node (ref "LED10") (pin "A") (pinfunction "A_A") (pintype "passive"))
    )
    (net (code "79") (name "unconnected-(LED13-C-PadK)") (class "Default")
      (node (ref "LED13") (pin "K") (pinfunction "C_K") (pintype "passive"))
    )
    (net (code "80") (name "unconnected-(LED13-PadA)") (class "Default")
      (node (ref "LED13") (pin "A") (pinfunction "A_A") (pintype "passive"))
    )
    (net (code "81") (name "unconnected-(Q1-B-Pad2)") (class "Default")
      (node (ref "Q1") (pin "2") (pinfunction "B_2") (pintype "passive"))
    )
    (net (code "82") (name "unconnected-(Q1-C-Pad1)") (class "Default")
      (node (ref "Q1") (pin "1") (pinfunction "C_1") (pintype "passive"))
    )
    (net (code "83") (name "unconnected-(Q1-E-Pad3)") (class "Default")
      (node (ref "Q1") (pin "3") (pinfunction "E_3") (pintype "passive"))
    )
    (net (code "84") (name "unconnected-(R3-Pad1)") (class "Default")
      (node (ref "R3") (pin "1") (pinfunction "1_1") (pintype "passive"))
    )
    (net (code "85") (name "unconnected-(R3-Pad2)") (class "Default")
      (node (ref "R3") (pin "2") (pinfunction "2_2") (pintype "passive"))
    )
    (net (code "86") (name "unconnected-(R10-Pad1)") (class "Default")
      (node (ref "R10") (pin "1") (pinfunction "1_1") (pintype "passive"))
    )
    (net (code "87") (name "unconnected-(R10-Pad2)") (class "Default")
      (node (ref "R10") (pin "2") (pinfunction "2_2") (pintype "passive"))
    )
    (net (code "88") (name "unconnected-(R17-Pad1)") (class "Default")
      (node (ref "R17") (pin "1") (pinfunction "1_1") (pintype "passive"))
    )
    (net (code "89") (name "unconnected-(R17-Pad2)") (class "Default")
      (node (ref "R17") (pin "2") (pinfunction "2_2") (pintype "passive"))
    )
    (net (code "90") (name "unconnected-(R22-Pad1)") (class "Default")
      (node (ref "R22") (pin "1") (pinfunction "1_1") (pintype "passive"))
    )
    (net (code "91") (name "unconnected-(R22-Pad2)") (class "Default")
      (node (ref "R22") (pin "2") (pinfunction "2_2") (pintype "passive"))
    )
    (net (code "92") (name "unconnected-(R25-Pad1)") (class "Default")
      (node (ref "R25") (pin "1") (pinfunction "1_1") (pintype "passive"))
    )
    (net (code "93") (name "unconnected-(S1-P-Pad3)") (class "Default")
      (node (ref "S1") (pin "3") (pinfunction "P_3") (pintype "passive"))
    )
    (net (code "94") (name "unconnected-(S1-P1-Pad4)") (class "Default")
      (node (ref "S1") (pin "4") (pinfunction "P1_4") (pintype "passive"))
    )
    (net (code "95") (name "unconnected-(S1-S-Pad1)") (class "Default")
      (node (ref "S1") (pin "1") (pinfunction "S_1") (pintype "passive"))
    )
    (net (code "96") (name "unconnected-(S1-S1-Pad2)") (class "Default")
      (node (ref "S1") (pin "2") (pinfunction "S1_2") (pintype "passive"))
    )
    (net (code "97") (name "unconnected-(S2-P-Pad3)") (class "Default")
      (node (ref "S2") (pin "3") (pinfunction "P_3") (pintype "passive"))
    )
    (net (code "98") (name "unconnected-(S2-P1-Pad4)") (class "Default")
      (node (ref "S2") (pin "4") (pinfunction "P1_4") (pintype "passive"))
    )
    (net (code "99") (name "unconnected-(S2-S-Pad1)") (class "Default")
      (node (ref "S2") (pin "1") (pinfunction "S_1") (pintype "passive"))
    )
    (net (code "100") (name "unconnected-(S2-S1-Pad2)") (class "Default")
      (node (ref "S2") (pin "2") (pinfunction "S1_2") (pintype "passive"))
    )
    (net (code "101") (name "unconnected-(S3-P-Pad3)") (class "Default")
      (node (ref "S3") (pin "3") (pinfunction "P_3") (pintype "passive"))
    )
    (net (code "102") (name "unconnected-(S3-P1-Pad4)") (class "Default")
      (node (ref "S3") (pin "4") (pinfunction "P1_4") (pintype "passive"))
    )
    (net (code "103") (name "unconnected-(S3-S-Pad1)") (class "Default")
      (node (ref "S3") (pin "1") (pinfunction "S_1") (pintype "passive"))
    )
    (net (code "104") (name "unconnected-(S3-S1-Pad2)") (class "Default")
      (node (ref "S3") (pin "2") (pinfunction "S1_2") (pintype "passive"))
    )
    (net (code "105") (name "unconnected-(S4-P-Pad3)") (class "Default")
      (node (ref "S4") (pin "3") (pinfunction "P_3") (pintype "passive"))
    )
    (net (code "106") (name "unconnected-(S4-P1-Pad4)") (class "Default")
      (node (ref "S4") (pin "4") (pinfunction "P1_4") (pintype "passive"))
    )
    (net (code "107") (name "unconnected-(S4-S-Pad1)") (class "Default")
      (node (ref "S4") (pin "1") (pinfunction "S_1") (pintype "passive"))
    )
    (net (code "108") (name "unconnected-(S4-S1-Pad2)") (class "Default")
      (node (ref "S4") (pin "2") (pinfunction "S1_2") (pintype "passive"))
    )
    (net (code "109") (name "unconnected-(S5-P-Pad3)") (class "Default")
      (node (ref "S5") (pin "3") (pinfunction "P_3") (pintype "passive"))
    )
    (net (code "110") (name "unconnected-(S5-P1-Pad4)") (class "Default")
      (node (ref "S5") (pin "4") (pinfunction "P1_4") (pintype "passive"))
    )
    (net (code "111") (name "unconnected-(S5-S-Pad1)") (class "Default")
      (node (ref "S5") (pin "1") (pinfunction "S_1") (pintype "passive"))
    )
    (net (code "112") (name "unconnected-(S5-S1-Pad2)") (class "Default")
      (node (ref "S5") (pin "2") (pinfunction "S1_2") (pintype "passive"))
    )
    (net (code "113") (name "unconnected-(S6-P-Pad3)") (class "Default")
      (node (ref "S6") (pin "3") (pinfunction "P_3") (pintype "passive"))
    )
    (net (code "114") (name "unconnected-(S6-P1-Pad4)") (class "Default")
      (node (ref "S6") (pin "4") (pinfunction "P1_4") (pintype "passive"))
    )
    (net (code "115") (name "unconnected-(S6-S-Pad1)") (class "Default")
      (node (ref "S6") (pin "1") (pinfunction "S_1") (pintype "passive"))
    )
    (net (code "116") (name "unconnected-(S6-S1-Pad2)") (class "Default")
      (node (ref "S6") (pin "2") (pinfunction "S1_2") (pintype "passive"))
    )
    (net (code "117") (name "unconnected-(S7-P-Pad3)") (class "Default")
      (node (ref "S7") (pin "3") (pinfunction "P_3") (pintype "passive"))
    )
    (net (code "118") (name "unconnected-(S7-P1-Pad4)") (class "Default")
      (node (ref "S7") (pin "4") (pinfunction "P1_4") (pintype "passive"))
    )
    (net (code "119") (name "unconnected-(S7-S-Pad1)") (class "Default")
      (node (ref "S7") (pin "1") (pinfunction "S_1") (pintype "passive"))
    )
    (net (code "120") (name "unconnected-(S7-S1-Pad2)") (class "Default")
      (node (ref "S7") (pin "2") (pinfunction "S1_2") (pintype "passive"))
    )
    (net (code "121") (name "unconnected-(T1-E-Pad3)") (class "Default")
      (node (ref "T1") (pin "3") (pinfunction "E_3") (pintype "passive"))
    )
    (net (code "122") (name "unconnected-(T2-E-Pad3)") (class "Default")
      (node (ref "T2") (pin "3") (pinfunction "E_3") (pintype "passive"))
    )
    (net (code "123") (name "unconnected-(T4-B-Pad2)") (class "Default")
      (node (ref "T4") (pin "2") (pinfunction "B_2") (pintype "passive"))
    )
    (net (code "124") (name "unconnected-(T4-C-Pad1)") (class "Default")
      (node (ref "T4") (pin "1") (pinfunction "C_1") (pintype "passive"))
    )
    (net (code "125") (name "unconnected-(T4-E-Pad3)") (class "Default")
      (node (ref "T4") (pin "3") (pinfunction "E_3") (pintype "passive"))
    )
  )
)
